# ir2104_V1_2.net
KiCad netlist of a schematic drawn in EasyEDA Pro
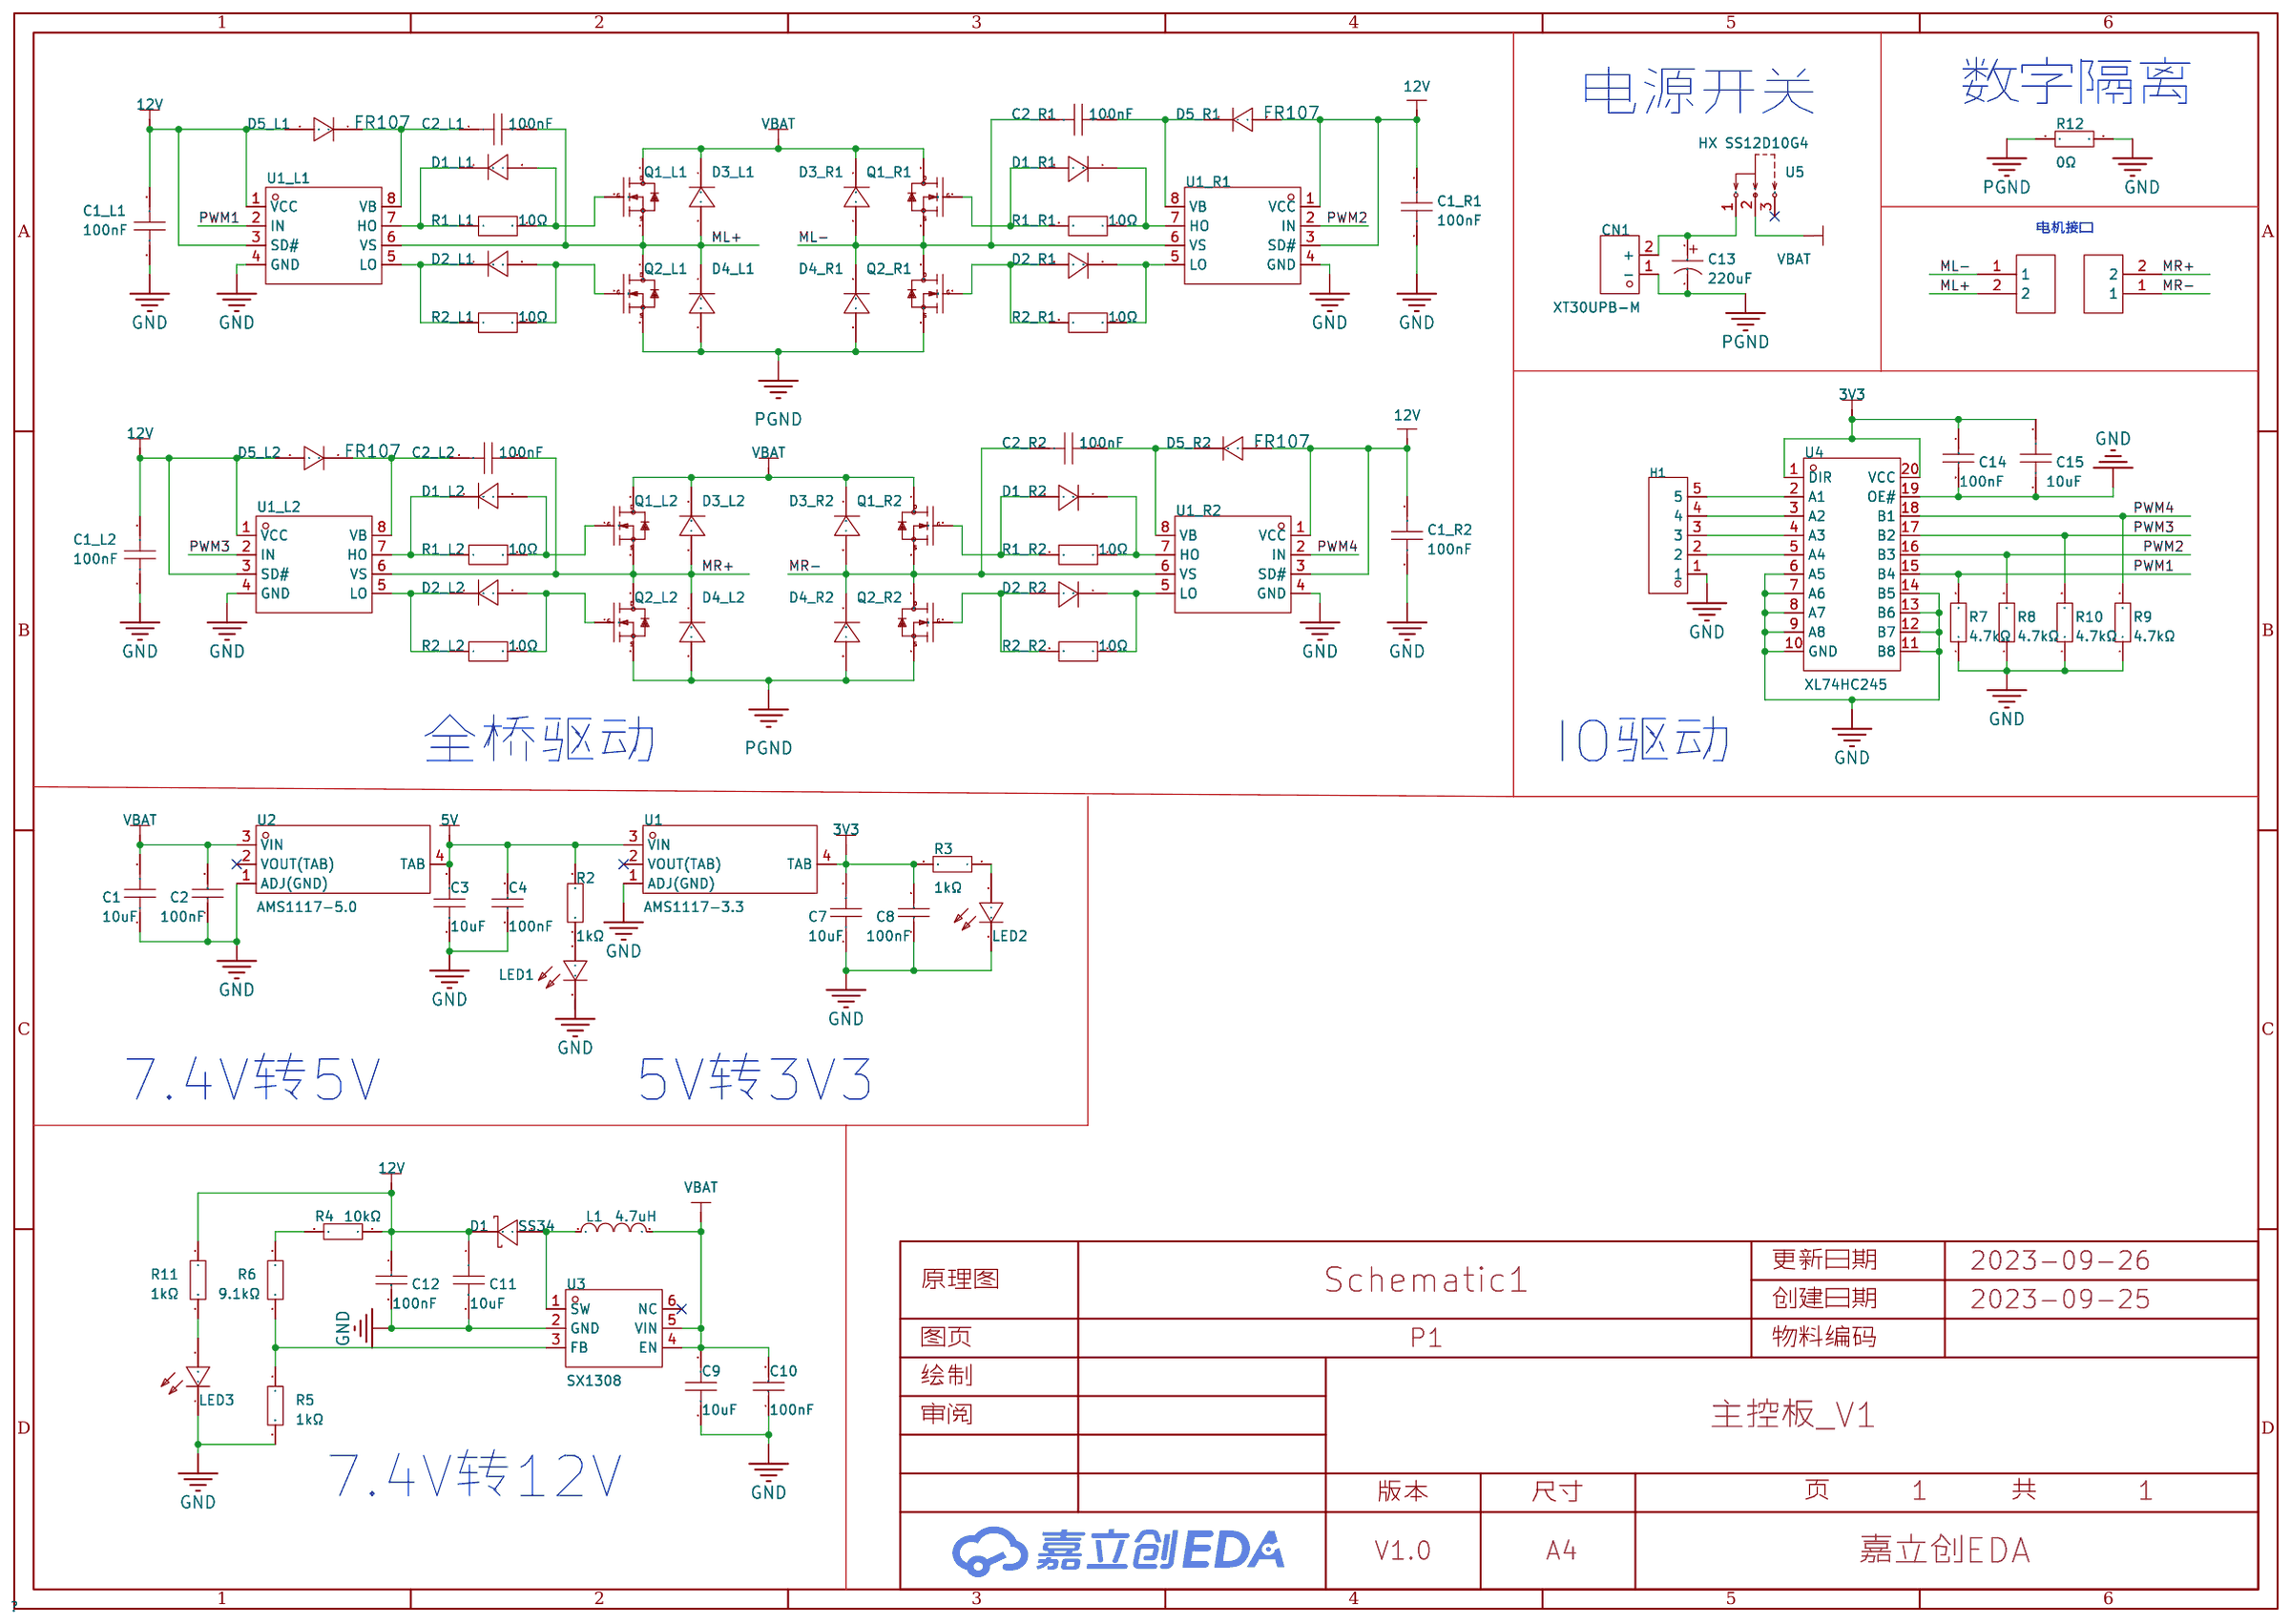
[diagram p0: schematic sheet]

(export (version "E")
  (design (tool "Eeschema 10.0.6"))
  (components
    (comp (ref "C1")
      (value "10uF")
      (footprint "easyedapro:C0603")
      (description "容值:10uF;精度:±20%;额定电压:25V;材质(温度系数):X5R;")
      (fields
        (field (name "Manufacturer Part") "CL10A106MA8NRNC")
        (field (name "Manufacturer") "SAMSUNG(三星)")
      )
      (libsource (lib "easyedapro") (part "CL10A106MA8NRNC"))
    )
    (comp (ref "C1_L1")
      (value "100nF")
      (footprint "easyedapro:C0603")
      (description "容值:100nF;精度:±10%;额定电压:50V;材质(温度系数):X7R;")
      (fields
        (field (name "Manufacturer Part") "CL10B104KB8NNNC")
        (field (name "Manufacturer") "SAMSUNG(三星)")
      )
      (libsource (lib "easyedapro") (part "CL10B104KB8NNNC"))
    )
    (comp (ref "C1_L2")
      (value "100nF")
      (footprint "easyedapro:C0603")
      (description "容值:100nF;精度:±10%;额定电压:50V;材质(温度系数):X7R;")
      (fields
        (field (name "Manufacturer Part") "CL10B104KB8NNNC")
        (field (name "Manufacturer") "SAMSUNG(三星)")
      )
      (libsource (lib "easyedapro") (part "CL10B104KB8NNNC"))
    )
    (comp (ref "C1_R1")
      (value "100nF")
      (footprint "easyedapro:C0603")
      (description "容值:100nF;精度:±10%;额定电压:50V;材质(温度系数):X7R;")
      (fields
        (field (name "Manufacturer Part") "CL10B104KB8NNNC")
        (field (name "Manufacturer") "SAMSUNG(三星)")
      )
      (libsource (lib "easyedapro") (part "CL10B104KB8NNNC"))
    )
    (comp (ref "C1_R2")
      (value "100nF")
      (footprint "easyedapro:C0603")
      (description "容值:100nF;精度:±10%;额定电压:50V;材质(温度系数):X7R;")
      (fields
        (field (name "Manufacturer Part") "CL10B104KB8NNNC")
        (field (name "Manufacturer") "SAMSUNG(三星)")
      )
      (libsource (lib "easyedapro") (part "CL10B104KB8NNNC"))
    )
    (comp (ref "C2")
      (value "100nF")
      (footprint "easyedapro:C0603")
      (description "容值:100nF;精度:±10%;额定电压:50V;材质(温度系数):X7R;")
      (fields (field (name "Manufacturer Part") "0603B104K500NT") (field (name "Manufacturer") "FH(风华)"))
      (libsource (lib "easyedapro") (part "0603B104K500NT"))
    )
    (comp (ref "C2_L1")
      (value "100nF")
      (footprint "easyedapro:C0603")
      (description "容值:100nF;精度:±10%;额定电压:50V;材质(温度系数):X7R;")
      (fields
        (field (name "Manufacturer Part") "CL10B104KB8NNNC")
        (field (name "Manufacturer") "SAMSUNG(三星)")
      )
      (libsource (lib "easyedapro") (part "CL10B104KB8NNNC"))
    )
    (comp (ref "C2_L2")
      (value "100nF")
      (footprint "easyedapro:C0603")
      (description "容值:100nF;精度:±10%;额定电压:50V;材质(温度系数):X7R;")
      (fields
        (field (name "Manufacturer Part") "CL10B104KB8NNNC")
        (field (name "Manufacturer") "SAMSUNG(三星)")
      )
      (libsource (lib "easyedapro") (part "CL10B104KB8NNNC"))
    )
    (comp (ref "C2_R1")
      (value "100nF")
      (footprint "easyedapro:C0603")
      (description "容值:100nF;精度:±10%;额定电压:50V;材质(温度系数):X7R;")
      (fields
        (field (name "Manufacturer Part") "CL10B104KB8NNNC")
        (field (name "Manufacturer") "SAMSUNG(三星)")
      )
      (libsource (lib "easyedapro") (part "CL10B104KB8NNNC"))
    )
    (comp (ref "C2_R2")
      (value "100nF")
      (footprint "easyedapro:C0603")
      (description "容值:100nF;精度:±10%;额定电压:50V;材质(温度系数):X7R;")
      (fields
        (field (name "Manufacturer Part") "CL10B104KB8NNNC")
        (field (name "Manufacturer") "SAMSUNG(三星)")
      )
      (libsource (lib "easyedapro") (part "CL10B104KB8NNNC"))
    )
    (comp (ref "C3")
      (value "10uF")
      (footprint "easyedapro:C0603")
      (description "容值:10uF;精度:±20%;额定电压:25V;材质(温度系数):X5R;")
      (fields
        (field (name "Manufacturer Part") "CL10A106MA8NRNC")
        (field (name "Manufacturer") "SAMSUNG(三星)")
      )
      (libsource (lib "easyedapro") (part "CL10A106MA8NRNC"))
    )
    (comp (ref "C4")
      (value "100nF")
      (footprint "easyedapro:C0603")
      (description "容值:100nF;精度:±10%;额定电压:50V;材质(温度系数):X7R;")
      (fields (field (name "Manufacturer Part") "0603B104K500NT") (field (name "Manufacturer") "FH(风华)"))
      (libsource (lib "easyedapro") (part "0603B104K500NT"))
    )
    (comp (ref "C7")
      (value "10uF")
      (footprint "easyedapro:C0603")
      (description "容值:10uF;精度:±20%;额定电压:25V;材质(温度系数):X5R;")
      (fields
        (field (name "Manufacturer Part") "CL10A106MA8NRNC")
        (field (name "Manufacturer") "SAMSUNG(三星)")
      )
      (libsource (lib "easyedapro") (part "CL10A106MA8NRNC"))
    )
    (comp (ref "C8")
      (value "100nF")
      (footprint "easyedapro:C0603")
      (description "容值:100nF;精度:±10%;额定电压:50V;材质(温度系数):X7R;")
      (fields (field (name "Manufacturer Part") "0603B104K500NT") (field (name "Manufacturer") "FH(风华)"))
      (libsource (lib "easyedapro") (part "0603B104K500NT"))
    )
    (comp (ref "C9")
      (value "10uF")
      (footprint "easyedapro:C0603")
      (description "容值:10uF;精度:±20%;额定电压:25V;材质(温度系数):X5R;")
      (fields
        (field (name "Manufacturer Part") "CL10A106MA8NRNC")
        (field (name "Manufacturer") "SAMSUNG(三星)")
      )
      (libsource (lib "easyedapro") (part "CL10A106MA8NRNC"))
    )
    (comp (ref "C10")
      (value "100nF")
      (footprint "easyedapro:C0603")
      (description "容值:100nF;精度:±10%;额定电压:50V;材质(温度系数):X7R;")
      (fields (field (name "Manufacturer Part") "0603B104K500NT") (field (name "Manufacturer") "FH(风华)"))
      (libsource (lib "easyedapro") (part "0603B104K500NT"))
    )
    (comp (ref "C11")
      (value "10uF")
      (footprint "easyedapro:C0603")
      (description "容值:10uF;精度:±20%;额定电压:25V;材质(温度系数):X5R;")
      (fields
        (field (name "Manufacturer Part") "CL10A106MA8NRNC")
        (field (name "Manufacturer") "SAMSUNG(三星)")
      )
      (libsource (lib "easyedapro") (part "CL10A106MA8NRNC"))
    )
    (comp (ref "C12")
      (value "100nF")
      (footprint "easyedapro:C0603")
      (description "容值:100nF;精度:±10%;额定电压:50V;材质(温度系数):X7R;")
      (fields (field (name "Manufacturer Part") "0603B104K500NT") (field (name "Manufacturer") "FH(风华)"))
      (libsource (lib "easyedapro") (part "0603B104K500NT"))
    )
    (comp (ref "C13")
      (value "220uF")
      (footprint "easyedapro:CAP-TH_BD8.0-P3.50-D0.6-FD")
      (description "容值:220uF;精度:±20%;额定电压:35V;纹波电流:-;等效串联电阻:-;")
      (fields
        (field (name "Manufacturer Part") "KM227M035F12RR0VH2FP0")
        (field (name "Manufacturer") "CX(承兴)")
      )
      (libsource (lib "easyedapro") (part "220uf/35V"))
    )
    (comp (ref "C14")
      (value "100nF")
      (footprint "easyedapro:C0603")
      (description "容值:100nF;精度:±10%;额定电压:50V;材质(温度系数):X7R;")
      (fields (field (name "Manufacturer Part") "0603B104K500NT") (field (name "Manufacturer") "FH(风华)"))
      (libsource (lib "easyedapro") (part "0603B104K500NT"))
    )
    (comp (ref "C15")
      (value "10uF")
      (footprint "easyedapro:C0603")
      (description "容值:10uF;精度:±20%;额定电压:25V;材质(温度系数):X5R;")
      (fields
        (field (name "Manufacturer Part") "CL10A106MA8NRNC")
        (field (name "Manufacturer") "SAMSUNG(三星)")
      )
      (libsource (lib "easyedapro") (part "CL10A106MA8NRNC"))
    )
    (comp (ref "CN1")
      (value "XT30UPB-M")
      (footprint "easyedapro:CONN-TH_XT30UPB-M")
      (fields (field (name "Manufacturer") "AMASS(艾迈斯)"))
      (libsource (lib "easyedapro") (part "XT30UPB-M"))
    )
    (comp (ref "D1")
      (value "SS34")
      (footprint "easyedapro:SMA_L4.3-W2.6-LS5.2-RD")
      (description "二极管配置:独立式;直流反向耐压(Vr):40V;平均整流电流(Io):3A;正向压降(Vf):550mV@3A;")
      (fields (field (name "Manufacturer") "MDD"))
      (libsource (lib "easyedapro") (part "SS34_C8678"))
    )
    (comp (ref "D1_L1")
      (value "US1M")
      (footprint "easyedapro:SMA_L4.4-W2.8-LS5.4-RD")
      (fields (field (name "Manufacturer") "MDD"))
      (libsource (lib "easyedapro") (part "US1MG_C412437"))
    )
    (comp (ref "D1_L2")
      (value "US1M")
      (footprint "easyedapro:SMA_L4.4-W2.8-LS5.4-RD")
      (fields (field (name "Manufacturer") "MDD"))
      (libsource (lib "easyedapro") (part "US1MG_C412437"))
    )
    (comp (ref "D1_R1")
      (value "US1M")
      (footprint "easyedapro:SMA_L4.4-W2.8-LS5.4-RD")
      (fields (field (name "Manufacturer") "MDD"))
      (libsource (lib "easyedapro") (part "US1MG_C412437"))
    )
    (comp (ref "D1_R2")
      (value "US1M")
      (footprint "easyedapro:SMA_L4.4-W2.8-LS5.4-RD")
      (fields (field (name "Manufacturer") "MDD"))
      (libsource (lib "easyedapro") (part "US1MG_C412437"))
    )
    (comp (ref "D2_L1")
      (value "US1M")
      (footprint "easyedapro:SMA_L4.4-W2.8-LS5.4-RD")
      (fields (field (name "Manufacturer") "MDD"))
      (libsource (lib "easyedapro") (part "US1MG_C412437"))
    )
    (comp (ref "D2_L2")
      (value "US1M")
      (footprint "easyedapro:SMA_L4.4-W2.8-LS5.4-RD")
      (fields (field (name "Manufacturer") "MDD"))
      (libsource (lib "easyedapro") (part "US1MG_C412437"))
    )
    (comp (ref "D2_R1")
      (value "US1M")
      (footprint "easyedapro:SMA_L4.4-W2.8-LS5.4-RD")
      (fields (field (name "Manufacturer") "MDD"))
      (libsource (lib "easyedapro") (part "US1MG_C412437"))
    )
    (comp (ref "D2_R2")
      (value "US1M")
      (footprint "easyedapro:SMA_L4.4-W2.8-LS5.4-RD")
      (fields (field (name "Manufacturer") "MDD"))
      (libsource (lib "easyedapro") (part "US1MG_C412437"))
    )
    (comp (ref "D3_L1")
      (value "US1M")
      (footprint "easyedapro:SMA_L4.4-W2.8-LS5.4-RD")
      (fields (field (name "Manufacturer") "MDD"))
      (libsource (lib "easyedapro") (part "US1MG_C412437"))
    )
    (comp (ref "D3_L2")
      (value "US1M")
      (footprint "easyedapro:SMA_L4.4-W2.8-LS5.4-RD")
      (fields (field (name "Manufacturer") "MDD"))
      (libsource (lib "easyedapro") (part "US1MG_C412437"))
    )
    (comp (ref "D3_R1")
      (value "US1M")
      (footprint "easyedapro:SMA_L4.4-W2.8-LS5.4-RD")
      (fields (field (name "Manufacturer") "MDD"))
      (libsource (lib "easyedapro") (part "US1MG_C412437"))
    )
    (comp (ref "D3_R2")
      (value "US1M")
      (footprint "easyedapro:SMA_L4.4-W2.8-LS5.4-RD")
      (fields (field (name "Manufacturer") "MDD"))
      (libsource (lib "easyedapro") (part "US1MG_C412437"))
    )
    (comp (ref "D4_L1")
      (value "US1M")
      (footprint "easyedapro:SMA_L4.4-W2.8-LS5.4-RD")
      (fields (field (name "Manufacturer") "MDD"))
      (libsource (lib "easyedapro") (part "US1MG_C412437"))
    )
    (comp (ref "D4_L2")
      (value "US1M")
      (footprint "easyedapro:SMA_L4.4-W2.8-LS5.4-RD")
      (fields (field (name "Manufacturer") "MDD"))
      (libsource (lib "easyedapro") (part "US1MG_C412437"))
    )
    (comp (ref "D4_R1")
      (value "US1M")
      (footprint "easyedapro:SMA_L4.4-W2.8-LS5.4-RD")
      (fields (field (name "Manufacturer") "MDD"))
      (libsource (lib "easyedapro") (part "US1MG_C412437"))
    )
    (comp (ref "D4_R2")
      (value "US1M")
      (footprint "easyedapro:SMA_L4.4-W2.8-LS5.4-RD")
      (fields (field (name "Manufacturer") "MDD"))
      (libsource (lib "easyedapro") (part "US1MG_C412437"))
    )
    (comp (ref "D5_L1")
      (value "FR107")
      (footprint "easyedapro:SOD-123_L2.8-W1.8-LS3.7-RD")
      (fields (field (name "Manufacturer") "BORN(伯恩半导体)"))
      (libsource (lib "easyedapro") (part "FR107_C511885"))
    )
    (comp (ref "D5_L2")
      (value "FR107")
      (footprint "easyedapro:SOD-123_L2.8-W1.8-LS3.7-RD")
      (fields (field (name "Manufacturer") "BORN(伯恩半导体)"))
      (libsource (lib "easyedapro") (part "FR107_C511885"))
    )
    (comp (ref "D5_R1")
      (value "FR107")
      (footprint "easyedapro:SOD-123_L2.8-W1.8-LS3.7-RD")
      (fields (field (name "Manufacturer") "BORN(伯恩半导体)"))
      (libsource (lib "easyedapro") (part "FR107_C511885"))
    )
    (comp (ref "D5_R2")
      (value "FR107")
      (footprint "easyedapro:SOD-123_L2.8-W1.8-LS3.7-RD")
      (fields (field (name "Manufacturer") "BORN(伯恩半导体)"))
      (libsource (lib "easyedapro") (part "FR107_C511885"))
    )
    (comp (ref "H1")
      (value "PZ254V-11-05P")
      (footprint "easyedapro:HDR-TH_5P-P2.54-V-M")
      (fields (field (name "Manufacturer") "XFCN(兴飞)"))
      (libsource (lib "easyedapro") (part "PZ254V-11-05P"))
    )
    (comp (ref "L1")
      (value "4.7uH")
      (footprint "easyedapro:IND-SMD_L5.4-W5.2_FXL0530")
      (description "电感值:4.7uH;精度:±20%;额定电流:4.5A;饱和电流(Isat):5A;")
      (fields (field (name "Manufacturer Part") "FXL0530-4R7-M") (field (name "Manufacturer") "cjiang(长江微电)"))
      (libsource (lib "easyedapro") (part "FXL0530-4R7-M"))
    )
    (comp (ref "LED1")
      (value "NCD0603R1")
      (footprint "easyedapro:LED0603-RD_RED")
      (description "发光颜色:红灯;")
      (fields (field (name "Manufacturer") "国星光电"))
      (libsource (lib "easyedapro") (part "FC-DA1608HRK-620D"))
    )
    (comp (ref "LED2")
      (value "NCD0603R1")
      (footprint "easyedapro:LED0603-RD_RED")
      (description "发光颜色:红灯;")
      (fields (field (name "Manufacturer") "国星光电"))
      (libsource (lib "easyedapro") (part "FC-DA1608HRK-620D"))
    )
    (comp (ref "LED3")
      (value "NCD0603R1")
      (footprint "easyedapro:LED0603-RD_RED")
      (description "发光颜色:红灯;")
      (fields (field (name "Manufacturer") "国星光电"))
      (libsource (lib "easyedapro") (part "FC-DA1608HRK-620D"))
    )
    (comp (ref "P1")
      (value "WJ500V-5.08-2P")
      (footprint "easyedapro:CONN-TH_2P-P5.00_WJ500V-5.08-2P")
      (fields (field (name "Manufacturer") "KANGNEX(康奈克斯电气)"))
      (libsource (lib "easyedapro") (part "WJ500V-5.08-2P-14-00A"))
    )
    (comp (ref "P2")
      (value "WJ500V-5.08-2P")
      (footprint "easyedapro:CONN-TH_2P-P5.00_WJ500V-5.08-2P")
      (fields (field (name "Manufacturer") "KANGNEX(康奈克斯电气)"))
      (libsource (lib "easyedapro") (part "WJ500V-5.08-2P-14-00A"))
    )
    (comp (ref "Q1_L1")
      (value "IRFR3607TRPBF")
      (footprint "easyedapro:TO-252-3_L6.5-W5.8-P4.58-BL")
      (fields (field (name "Manufacturer") "Infineon(英飞凌)"))
      (libsource (lib "easyedapro") (part "IRFR3607TRPBF"))
    )
    (comp (ref "Q1_L2")
      (value "IRFR3607TRPBF")
      (footprint "easyedapro:TO-252-3_L6.5-W5.8-P4.58-BL")
      (fields (field (name "Manufacturer") "Infineon(英飞凌)"))
      (libsource (lib "easyedapro") (part "IRFR3607TRPBF"))
    )
    (comp (ref "Q1_R1")
      (value "IRFR3607TRPBF")
      (footprint "easyedapro:TO-252-3_L6.5-W5.8-P4.58-BL")
      (fields (field (name "Manufacturer") "Infineon(英飞凌)"))
      (libsource (lib "easyedapro") (part "IRFR3607TRPBF"))
    )
    (comp (ref "Q1_R2")
      (value "IRFR3607TRPBF")
      (footprint "easyedapro:TO-252-3_L6.5-W5.8-P4.58-BL")
      (fields (field (name "Manufacturer") "Infineon(英飞凌)"))
      (libsource (lib "easyedapro") (part "IRFR3607TRPBF"))
    )
    (comp (ref "Q2_L1")
      (value "IRFR3607TRPBF")
      (footprint "easyedapro:TO-252-3_L6.5-W5.8-P4.58-BL")
      (fields (field (name "Manufacturer") "Infineon(英飞凌)"))
      (libsource (lib "easyedapro") (part "IRFR3607TRPBF"))
    )
    (comp (ref "Q2_L2")
      (value "IRFR3607TRPBF")
      (footprint "easyedapro:TO-252-3_L6.5-W5.8-P4.58-BL")
      (fields (field (name "Manufacturer") "Infineon(英飞凌)"))
      (libsource (lib "easyedapro") (part "IRFR3607TRPBF"))
    )
    (comp (ref "Q2_R1")
      (value "IRFR3607TRPBF")
      (footprint "easyedapro:TO-252-3_L6.5-W5.8-P4.58-BL")
      (fields (field (name "Manufacturer") "Infineon(英飞凌)"))
      (libsource (lib "easyedapro") (part "IRFR3607TRPBF"))
    )
    (comp (ref "Q2_R2")
      (value "IRFR3607TRPBF")
      (footprint "easyedapro:TO-252-3_L6.5-W5.8-P4.58-BL")
      (fields (field (name "Manufacturer") "Infineon(英飞凌)"))
      (libsource (lib "easyedapro") (part "IRFR3607TRPBF"))
    )
    (comp (ref "R1_L1")
      (value "10Ω")
      (footprint "easyedapro:R0603")
      (description "阻值:10Ω;精度:±0.5%;功率:250mW;")
      (fields (field (name "Manufacturer Part") "ERJUP3D10R0V") (field (name "Manufacturer") "PANASONIC(松下)"))
      (libsource (lib "easyedapro") (part "ERJUP3D10R0V"))
    )
    (comp (ref "R1_L2")
      (value "10Ω")
      (footprint "easyedapro:R0603")
      (description "阻值:10Ω;精度:±0.5%;功率:250mW;")
      (fields (field (name "Manufacturer Part") "ERJUP3D10R0V") (field (name "Manufacturer") "PANASONIC(松下)"))
      (libsource (lib "easyedapro") (part "ERJUP3D10R0V"))
    )
    (comp (ref "R1_R1")
      (value "10Ω")
      (footprint "easyedapro:R0603")
      (description "阻值:10Ω;精度:±0.5%;功率:250mW;")
      (fields (field (name "Manufacturer Part") "ERJUP3D10R0V") (field (name "Manufacturer") "PANASONIC(松下)"))
      (libsource (lib "easyedapro") (part "ERJUP3D10R0V"))
    )
    (comp (ref "R1_R2")
      (value "10Ω")
      (footprint "easyedapro:R0603")
      (description "阻值:10Ω;精度:±0.5%;功率:250mW;")
      (fields (field (name "Manufacturer Part") "ERJUP3D10R0V") (field (name "Manufacturer") "PANASONIC(松下)"))
      (libsource (lib "easyedapro") (part "ERJUP3D10R0V"))
    )
    (comp (ref "R2")
      (value "1kΩ")
      (footprint "easyedapro:R0603")
      (description "电阻类型:厚膜电阻;阻值:1kΩ;精度:±1%;功率:100mW;")
      (fields
        (field (name "Manufacturer Part") "0603WAF1001T5E")
        (field (name "Manufacturer") "UNI-ROYAL(厚声)")
      )
      (libsource (lib "easyedapro") (part "0603WAF1001T5E"))
    )
    (comp (ref "R2_L1")
      (value "10Ω")
      (footprint "easyedapro:R0603")
      (description "阻值:10Ω;精度:±0.5%;功率:250mW;")
      (fields (field (name "Manufacturer Part") "ERJUP3D10R0V") (field (name "Manufacturer") "PANASONIC(松下)"))
      (libsource (lib "easyedapro") (part "ERJUP3D10R0V"))
    )
    (comp (ref "R2_L2")
      (value "10Ω")
      (footprint "easyedapro:R0603")
      (description "阻值:10Ω;精度:±0.5%;功率:250mW;")
      (fields (field (name "Manufacturer Part") "ERJUP3D10R0V") (field (name "Manufacturer") "PANASONIC(松下)"))
      (libsource (lib "easyedapro") (part "ERJUP3D10R0V"))
    )
    (comp (ref "R2_R1")
      (value "10Ω")
      (footprint "easyedapro:R0603")
      (description "阻值:10Ω;精度:±0.5%;功率:250mW;")
      (fields (field (name "Manufacturer Part") "ERJUP3D10R0V") (field (name "Manufacturer") "PANASONIC(松下)"))
      (libsource (lib "easyedapro") (part "ERJUP3D10R0V"))
    )
    (comp (ref "R2_R2")
      (value "10Ω")
      (footprint "easyedapro:R0603")
      (description "阻值:10Ω;精度:±0.5%;功率:250mW;")
      (fields (field (name "Manufacturer Part") "ERJUP3D10R0V") (field (name "Manufacturer") "PANASONIC(松下)"))
      (libsource (lib "easyedapro") (part "ERJUP3D10R0V"))
    )
    (comp (ref "R3")
      (value "1kΩ")
      (footprint "easyedapro:R0603")
      (description "电阻类型:厚膜电阻;阻值:1kΩ;精度:±1%;功率:100mW;")
      (fields
        (field (name "Manufacturer Part") "0603WAF1001T5E")
        (field (name "Manufacturer") "UNI-ROYAL(厚声)")
      )
      (libsource (lib "easyedapro") (part "0603WAF1001T5E"))
    )
    (comp (ref "R4")
      (value "10kΩ")
      (footprint "easyedapro:R0603")
      (description "电阻类型:薄膜电阻;阻值:10kΩ;精度:±0.1%;功率:100mW;")
      (fields (field (name "Manufacturer Part") "RT0603BRD0710KL") (field (name "Manufacturer") "YAGEO(国巨)"))
      (libsource (lib "easyedapro") (part "RT0603BRD0710KL"))
    )
    (comp (ref "R5")
      (value "1kΩ")
      (footprint "easyedapro:R0603")
      (description "电阻类型:薄膜电阻;阻值:1kΩ;精度:±0.1%;功率:100mW;")
      (fields (field (name "Manufacturer Part") "RT0603BRD071KL") (field (name "Manufacturer") "YAGEO(国巨)"))
      (libsource (lib "easyedapro") (part "RT0603BRD071KL"))
    )
    (comp (ref "R6")
      (value "9.1kΩ")
      (footprint "easyedapro:R0603")
      (description "电阻类型:薄膜电阻;阻值:9.1kΩ;精度:±0.1%;功率:100mW;")
      (fields (field (name "Manufacturer Part") "PTFR0603B9K10P9") (field (name "Manufacturer") "RESI(开步睿思）"))
      (libsource (lib "easyedapro") (part "PTFR0603B9K10P9"))
    )
    (comp (ref "R7")
      (value "4.7kΩ")
      (footprint "easyedapro:R0603")
      (description "电阻类型:厚膜电阻;阻值:4.7kΩ;精度:±1%;功率:100mW;")
      (fields
        (field (name "Manufacturer Part") "0603WAF4701T5E")
        (field (name "Manufacturer") "UNI-ROYAL(厚声)")
      )
      (libsource (lib "easyedapro") (part "0603WAF4701T5E"))
    )
    (comp (ref "R8")
      (value "4.7kΩ")
      (footprint "easyedapro:R0603")
      (description "电阻类型:厚膜电阻;阻值:4.7kΩ;精度:±1%;功率:100mW;")
      (fields
        (field (name "Manufacturer Part") "0603WAF4701T5E")
        (field (name "Manufacturer") "UNI-ROYAL(厚声)")
      )
      (libsource (lib "easyedapro") (part "0603WAF4701T5E"))
    )
    (comp (ref "R9")
      (value "4.7kΩ")
      (footprint "easyedapro:R0603")
      (description "电阻类型:厚膜电阻;阻值:4.7kΩ;精度:±1%;功率:100mW;")
      (fields
        (field (name "Manufacturer Part") "0603WAF4701T5E")
        (field (name "Manufacturer") "UNI-ROYAL(厚声)")
      )
      (libsource (lib "easyedapro") (part "0603WAF4701T5E"))
    )
    (comp (ref "R10")
      (value "4.7kΩ")
      (footprint "easyedapro:R0603")
      (description "电阻类型:厚膜电阻;阻值:4.7kΩ;精度:±1%;功率:100mW;")
      (fields
        (field (name "Manufacturer Part") "0603WAF4701T5E")
        (field (name "Manufacturer") "UNI-ROYAL(厚声)")
      )
      (libsource (lib "easyedapro") (part "0603WAF4701T5E"))
    )
    (comp (ref "R11")
      (value "1kΩ")
      (footprint "easyedapro:R0603")
      (description "电阻类型:厚膜电阻;阻值:1kΩ;精度:±1%;功率:100mW;")
      (fields
        (field (name "Manufacturer Part") "0603WAF1001T5E")
        (field (name "Manufacturer") "UNI-ROYAL(厚声)")
      )
      (libsource (lib "easyedapro") (part "0603WAF1001T5E"))
    )
    (comp (ref "R12")
      (value "0Ω")
      (footprint "easyedapro:R0805")
      (description "电阻类型:厚膜电阻;阻值:0Ω;精度:±1%;功率:125mW;")
      (fields
        (field (name "Manufacturer Part") "0805W8F0000T5E")
        (field (name "Manufacturer") "UNI-ROYAL(厚声)")
      )
      (libsource (lib "easyedapro") (part "0805W8F0000T5E"))
    )
    (comp (ref "U1")
      (value "AMS1117-3.3")
      (footprint "easyedapro:SOT-223-4_L6.5-W3.5-P2.30-LS7.0-BR")
      (description "输出类型:固定;输出极性:正;最大输入电压:18V;输出电压:3.3V;输出电流:1A;电源纹波抑制比(PSRR):60dB@(120Hz);")
      (fields (field (name "Manufacturer") "UMW(广东友台半导体)"))
      (libsource (lib "easyedapro") (part "AMS1117-3.3_C347222"))
    )
    (comp (ref "U1_L1")
      (value "EG2104")
      (footprint "easyedapro:SOP-8_L5.0-W4.0-P1.27-LS6.2-BL")
      (description "高性价比, 600V，半桥式Nmos预驱动器")
      (fields (field (name "Manufacturer") "EG(屹晶微)"))
      (libsource (lib "easyedapro") (part "EG2104"))
    )
    (comp (ref "U1_L2")
      (value "EG2104")
      (footprint "easyedapro:SOP-8_L5.0-W4.0-P1.27-LS6.2-BL")
      (description "高性价比, 600V，半桥式Nmos预驱动器")
      (fields (field (name "Manufacturer") "EG(屹晶微)"))
      (libsource (lib "easyedapro") (part "EG2104"))
    )
    (comp (ref "U1_R1")
      (value "EG2104")
      (footprint "easyedapro:SOP-8_L5.0-W4.0-P1.27-LS6.2-BL")
      (description "高性价比, 600V，半桥式Nmos预驱动器")
      (fields (field (name "Manufacturer") "EG(屹晶微)"))
      (libsource (lib "easyedapro") (part "EG2104"))
    )
    (comp (ref "U1_R2")
      (value "EG2104")
      (footprint "easyedapro:SOP-8_L5.0-W4.0-P1.27-LS6.2-BL")
      (description "高性价比, 600V，半桥式Nmos预驱动器")
      (fields (field (name "Manufacturer") "EG(屹晶微)"))
      (libsource (lib "easyedapro") (part "EG2104"))
    )
    (comp (ref "U2")
      (value "AMS1117-5.0")
      (footprint "easyedapro:SOT-223_L6.7-W3.5-P2.30-BR")
      (description "输出类型:固定;输出极性:正;最大输入电压:18V;输出电压:5V;输出电流:1A;电源纹波抑制比(PSRR):60dB@(120Hz);")
      (fields (field (name "Manufacturer") "UMW(广东友台半导体)"))
      (libsource (lib "easyedapro") (part "AMS1117-5.0_C347223"))
    )
    (comp (ref "U3")
      (value "SX1308")
      (footprint "easyedapro:SOT-23-6_L2.9-W1.6-P0.95-LS2.8-BL")
      (description "功能类型:升压型;同步整流:否;输出通道数:1;拓扑结构:升压式;输入电压:2V~24V;输出电压:28V;输出电流(最大值):-;开关频率:1.2MHz;")
      (fields (field (name "Manufacturer") "SX(硕芯科技)"))
      (libsource (lib "easyedapro") (part "SX1308"))
    )
    (comp (ref "U4")
      (value "XL74HC245")
      (footprint "easyedapro:SOP-20_L12.8-W7.5-P1.27-LS10.4-BL")
      (description "八路总线收发器")
      (fields (field (name "Manufacturer") "XINLUDA(信路达)"))
      (libsource (lib "easyedapro") (part "XL74HC245"))
    )
    (comp (ref "U5")
      (value "HX SS12D10G4")
      (footprint "easyedapro:SW-TH_SHOU-HAN_SS12D10G4")
      (fields (field (name "Manufacturer") "hanxia(韩下)"))
      (libsource (lib "easyedapro") (part "HX SS12D10G4"))
    )
  )
  (nets
    (net (code "1") (name "/ML+") (class "Default")
      (node (ref "C2_L1") (pin "2") (pinfunction "2_2") (pintype "input"))
      (node (ref "D3_L1") (pin "2") (pinfunction "A_2") (pintype "input"))
      (node (ref "D4_L1") (pin "1") (pinfunction "C_1") (pintype "input"))
      (node (ref "P1") (pin "2") (pinfunction "2_2") (pintype "input"))
      (node (ref "Q1_L1") (pin "3") (pinfunction "S_3") (pintype "input"))
      (node (ref "Q2_L1") (pin "2") (pinfunction "D_2") (pintype "input"))
      (node (ref "U1_L1") (pin "6") (pinfunction "VS_6") (pintype "input"))
    )
    (net (code "2") (name "/ML-") (class "Default")
      (node (ref "C2_R1") (pin "2") (pinfunction "2_2") (pintype "input"))
      (node (ref "D3_R1") (pin "2") (pinfunction "A_2") (pintype "input"))
      (node (ref "D4_R1") (pin "1") (pinfunction "C_1") (pintype "input"))
      (node (ref "P1") (pin "1") (pinfunction "1_1") (pintype "input"))
      (node (ref "Q1_R1") (pin "3") (pinfunction "S_3") (pintype "input"))
      (node (ref "Q2_R1") (pin "2") (pinfunction "D_2") (pintype "input"))
      (node (ref "U1_R1") (pin "6") (pinfunction "VS_6") (pintype "input"))
    )
    (net (code "3") (name "/MR+") (class "Default")
      (node (ref "C2_L2") (pin "2") (pinfunction "2_2") (pintype "input"))
      (node (ref "D3_L2") (pin "2") (pinfunction "A_2") (pintype "input"))
      (node (ref "D4_L2") (pin "1") (pinfunction "C_1") (pintype "input"))
      (node (ref "P2") (pin "2") (pinfunction "2_2") (pintype "input"))
      (node (ref "Q1_L2") (pin "3") (pinfunction "S_3") (pintype "input"))
      (node (ref "Q2_L2") (pin "2") (pinfunction "D_2") (pintype "input"))
      (node (ref "U1_L2") (pin "6") (pinfunction "VS_6") (pintype "input"))
    )
    (net (code "4") (name "/MR-") (class "Default")
      (node (ref "C2_R2") (pin "2") (pinfunction "2_2") (pintype "input"))
      (node (ref "D3_R2") (pin "2") (pinfunction "A_2") (pintype "input"))
      (node (ref "D4_R2") (pin "1") (pinfunction "C_1") (pintype "input"))
      (node (ref "P2") (pin "1") (pinfunction "1_1") (pintype "input"))
      (node (ref "Q1_R2") (pin "3") (pinfunction "S_3") (pintype "input"))
      (node (ref "Q2_R2") (pin "2") (pinfunction "D_2") (pintype "input"))
      (node (ref "U1_R2") (pin "6") (pinfunction "VS_6") (pintype "input"))
    )
    (net (code "5") (name "/PWM1") (class "Default")
      (node (ref "R7") (pin "2") (pinfunction "2_2") (pintype "input"))
      (node (ref "U1_L1") (pin "2") (pinfunction "IN_2") (pintype "input"))
      (node (ref "U4") (pin "15") (pinfunction "B4_15") (pintype "input"))
    )
    (net (code "6") (name "/PWM2") (class "Default")
      (node (ref "R8") (pin "2") (pinfunction "2_2") (pintype "input"))
      (node (ref "U1_R1") (pin "2") (pinfunction "IN_2") (pintype "input"))
      (node (ref "U4") (pin "16") (pinfunction "B3_16") (pintype "input"))
    )
    (net (code "7") (name "/PWM3") (class "Default")
      (node (ref "R10") (pin "2") (pinfunction "2_2") (pintype "input"))
      (node (ref "U1_L2") (pin "2") (pinfunction "IN_2") (pintype "input"))
      (node (ref "U4") (pin "17") (pinfunction "B2_17") (pintype "input"))
    )
    (net (code "8") (name "/PWM4") (class "Default")
      (node (ref "R9") (pin "2") (pinfunction "2_2") (pintype "input"))
      (node (ref "U1_R2") (pin "2") (pinfunction "IN_2") (pintype "input"))
      (node (ref "U4") (pin "18") (pinfunction "B1_18") (pintype "input"))
    )
    (net (code "9") (name "3V3") (class "Default")
      (node (ref "C14") (pin "1") (pinfunction "1_1") (pintype "input"))
      (node (ref "C15") (pin "1") (pinfunction "1_1") (pintype "input"))
      (node (ref "C7") (pin "2") (pinfunction "2_2") (pintype "input"))
      (node (ref "C8") (pin "2") (pinfunction "2_2") (pintype "input"))
      (node (ref "R3") (pin "2") (pinfunction "2_2") (pintype "input"))
      (node (ref "U1") (pin "4") (pinfunction "TAB_4") (pintype "input"))
      (node (ref "U4") (pin "1") (pinfunction "DIR_1") (pintype "input"))
      (node (ref "U4") (pin "20") (pinfunction "VCC_20") (pintype "input"))
    )
    (net (code "10") (name "5V") (class "Default")
      (node (ref "C3") (pin "2") (pinfunction "2_2") (pintype "input"))
      (node (ref "C4") (pin "2") (pinfunction "2_2") (pintype "input"))
      (node (ref "R2") (pin "1") (pinfunction "1_1") (pintype "input"))
      (node (ref "U1") (pin "3") (pinfunction "VIN_3") (pintype "input"))
      (node (ref "U2") (pin "4") (pinfunction "TAB_4") (pintype "input"))
    )
    (net (code "11") (name "12V") (class "Default")
      (node (ref "C11") (pin "1") (pinfunction "1_1") (pintype "input"))
      (node (ref "C12") (pin "1") (pinfunction "1_1") (pintype "input"))
      (node (ref "C1_L1") (pin "2") (pinfunction "2_2") (pintype "input"))
      (node (ref "C1_L2") (pin "2") (pinfunction "2_2") (pintype "input"))
      (node (ref "C1_R1") (pin "2") (pinfunction "2_2") (pintype "input"))
      (node (ref "C1_R2") (pin "2") (pinfunction "2_2") (pintype "input"))
      (node (ref "D1") (pin "1") (pinfunction "K_1") (pintype "input"))
      (node (ref "D5_L1") (pin "2") (pinfunction "A_2") (pintype "input"))
      (node (ref "D5_L2") (pin "2") (pinfunction "A_2") (pintype "input"))
      (node (ref "D5_R1") (pin "2") (pinfunction "A_2") (pintype "input"))
      (node (ref "D5_R2") (pin "2") (pinfunction "A_2") (pintype "input"))
      (node (ref "R11") (pin "1") (pinfunction "1_1") (pintype "input"))
      (node (ref "R4") (pin "1") (pinfunction "1_1") (pintype "input"))
      (node (ref "U1_L1") (pin "1") (pinfunction "VCC_1") (pintype "input"))
      (node (ref "U1_L1") (pin "3") (pinfunction "SD#_3") (pintype "input"))
      (node (ref "U1_L2") (pin "1") (pinfunction "VCC_1") (pintype "input"))
      (node (ref "U1_L2") (pin "3") (pinfunction "SD#_3") (pintype "input"))
      (node (ref "U1_R1") (pin "1") (pinfunction "VCC_1") (pintype "input"))
      (node (ref "U1_R1") (pin "3") (pinfunction "SD#_3") (pintype "input"))
      (node (ref "U1_R2") (pin "1") (pinfunction "VCC_1") (pintype "input"))
      (node (ref "U1_R2") (pin "3") (pinfunction "SD#_3") (pintype "input"))
    )
    (net (code "12") (name "GND") (class "Default")
      (node (ref "C1") (pin "1") (pinfunction "1_1") (pintype "input"))
      (node (ref "C10") (pin "1") (pinfunction "1_1") (pintype "input"))
      (node (ref "C11") (pin "2") (pinfunction "2_2") (pintype "input"))
      (node (ref "C12") (pin "2") (pinfunction "2_2") (pintype "input"))
      (node (ref "C14") (pin "2") (pinfunction "2_2") (pintype "input"))
      (node (ref "C15") (pin "2") (pinfunction "2_2") (pintype "input"))
      (node (ref "C1_L1") (pin "1") (pinfunction "1_1") (pintype "input"))
      (node (ref "C1_L2") (pin "1") (pinfunction "1_1") (pintype "input"))
      (node (ref "C1_R1") (pin "1") (pinfunction "1_1") (pintype "input"))
      (node (ref "C1_R2") (pin "1") (pinfunction "1_1") (pintype "input"))
      (node (ref "C2") (pin "1") (pinfunction "1_1") (pintype "input"))
      (node (ref "C3") (pin "1") (pinfunction "1_1") (pintype "input"))
      (node (ref "C4") (pin "1") (pinfunction "1_1") (pintype "input"))
      (node (ref "C7") (pin "1") (pinfunction "1_1") (pintype "input"))
      (node (ref "C8") (pin "1") (pinfunction "1_1") (pintype "input"))
      (node (ref "C9") (pin "1") (pinfunction "1_1") (pintype "input"))
      (node (ref "H1") (pin "1") (pinfunction "1_1") (pintype "input"))
      (node (ref "LED1") (pin "1") (pinfunction "K_1") (pintype "input"))
      (node (ref "LED2") (pin "1") (pinfunction "K_1") (pintype "input"))
      (node (ref "LED3") (pin "1") (pinfunction "K_1") (pintype "input"))
      (node (ref "R10") (pin "1") (pinfunction "1_1") (pintype "input"))
      (node (ref "R12") (pin "2") (pinfunction "2_2") (pintype "input"))
      (node (ref "R5") (pin "2") (pinfunction "2_2") (pintype "input"))
      (node (ref "R7") (pin "1") (pinfunction "1_1") (pintype "input"))
      (node (ref "R8") (pin "1") (pinfunction "1_1") (pintype "input"))
      (node (ref "R9") (pin "1") (pinfunction "1_1") (pintype "input"))
      (node (ref "U1") (pin "1") (pinfunction "ADJ(GND)_1") (pintype "input"))
      (node (ref "U1_L1") (pin "4") (pinfunction "GND_4") (pintype "input"))
      (node (ref "U1_L2") (pin "4") (pinfunction "GND_4") (pintype "input"))
      (node (ref "U1_R1") (pin "4") (pinfunction "GND_4") (pintype "input"))
      (node (ref "U1_R2") (pin "4") (pinfunction "GND_4") (pintype "input"))
      (node (ref "U2") (pin "1") (pinfunction "ADJ(GND)_1") (pintype "input"))
      (node (ref "U3") (pin "2") (pinfunction "GND_2") (pintype "input"))
      (node (ref "U4") (pin "10") (pinfunction "GND_10") (pintype "input"))
      (node (ref "U4") (pin "11") (pinfunction "B8_11") (pintype "input"))
      (node (ref "U4") (pin "12") (pinfunction "B7_12") (pintype "input"))
      (node (ref "U4") (pin "13") (pinfunction "B6_13") (pintype "input"))
      (node (ref "U4") (pin "14") (pinfunction "B5_14") (pintype "input"))
      (node (ref "U4") (pin "19") (pinfunction "OE#_19") (pintype "input"))
      (node (ref "U4") (pin "6") (pinfunction "A5_6") (pintype "input"))
      (node (ref "U4") (pin "7") (pinfunction "A6_7") (pintype "input"))
      (node (ref "U4") (pin "8") (pinfunction "A7_8") (pintype "input"))
      (node (ref "U4") (pin "9") (pinfunction "A8_9") (pintype "input"))
    )
    (net (code "13") (name "Net-(CN1-+)") (class "Default")
      (node (ref "C13") (pin "1") (pinfunction "1_1") (pintype "input"))
      (node (ref "CN1") (pin "2") (pinfunction "+_2") (pintype "input"))
      (node (ref "U5") (pin "1") (pinfunction "1_1") (pintype "input"))
    )
    (net (code "14") (name "Net-(D1-A)") (class "Default")
      (node (ref "D1") (pin "2") (pinfunction "A_2") (pintype "input"))
      (node (ref "L1") (pin "1") (pinfunction "1_1") (pintype "input"))
      (node (ref "U3") (pin "1") (pinfunction "SW_1") (pintype "input"))
    )
    (net (code "15") (name "Net-(D1_L1-A)") (class "Default")
      (node (ref "D1_L1") (pin "2") (pinfunction "A_2") (pintype "input"))
      (node (ref "Q1_L1") (pin "1") (pinfunction "G_1") (pintype "input"))
      (node (ref "R1_L1") (pin "2") (pinfunction "2_2") (pintype "input"))
    )
    (net (code "16") (name "Net-(D1_L1-C)") (class "Default")
      (node (ref "D1_L1") (pin "1") (pinfunction "C_1") (pintype "input"))
      (node (ref "R1_L1") (pin "1") (pinfunction "1_1") (pintype "input"))
      (node (ref "U1_L1") (pin "7") (pinfunction "HO_7") (pintype "input"))
    )
    (net (code "17") (name "Net-(D1_L2-A)") (class "Default")
      (node (ref "D1_L2") (pin "2") (pinfunction "A_2") (pintype "input"))
      (node (ref "Q1_L2") (pin "1") (pinfunction "G_1") (pintype "input"))
      (node (ref "R1_L2") (pin "2") (pinfunction "2_2") (pintype "input"))
    )
    (net (code "18") (name "Net-(D1_L2-C)") (class "Default")
      (node (ref "D1_L2") (pin "1") (pinfunction "C_1") (pintype "input"))
      (node (ref "R1_L2") (pin "1") (pinfunction "1_1") (pintype "input"))
      (node (ref "U1_L2") (pin "7") (pinfunction "HO_7") (pintype "input"))
    )
    (net (code "19") (name "Net-(D1_R1-A)") (class "Default")
      (node (ref "D1_R1") (pin "2") (pinfunction "A_2") (pintype "input"))
      (node (ref "Q1_R1") (pin "1") (pinfunction "G_1") (pintype "input"))
      (node (ref "R1_R1") (pin "2") (pinfunction "2_2") (pintype "input"))
    )
    (net (code "20") (name "Net-(D1_R1-C)") (class "Default")
      (node (ref "D1_R1") (pin "1") (pinfunction "C_1") (pintype "input"))
      (node (ref "R1_R1") (pin "1") (pinfunction "1_1") (pintype "input"))
      (node (ref "U1_R1") (pin "7") (pinfunction "HO_7") (pintype "input"))
    )
    (net (code "21") (name "Net-(D1_R2-A)") (class "Default")
      (node (ref "D1_R2") (pin "2") (pinfunction "A_2") (pintype "input"))
      (node (ref "Q1_R2") (pin "1") (pinfunction "G_1") (pintype "input"))
      (node (ref "R1_R2") (pin "2") (pinfunction "2_2") (pintype "input"))
    )
    (net (code "22") (name "Net-(D1_R2-C)") (class "Default")
      (node (ref "D1_R2") (pin "1") (pinfunction "C_1") (pintype "input"))
      (node (ref "R1_R2") (pin "1") (pinfunction "1_1") (pintype "input"))
      (node (ref "U1_R2") (pin "7") (pinfunction "HO_7") (pintype "input"))
    )
    (net (code "23") (name "Net-(D2_L1-A)") (class "Default")
      (node (ref "D2_L1") (pin "2") (pinfunction "A_2") (pintype "input"))
      (node (ref "Q2_L1") (pin "1") (pinfunction "G_1") (pintype "input"))
      (node (ref "R2_L1") (pin "2") (pinfunction "2_2") (pintype "input"))
    )
    (net (code "24") (name "Net-(D2_L1-C)") (class "Default")
      (node (ref "D2_L1") (pin "1") (pinfunction "C_1") (pintype "input"))
      (node (ref "R2_L1") (pin "1") (pinfunction "1_1") (pintype "input"))
      (node (ref "U1_L1") (pin "5") (pinfunction "LO_5") (pintype "input"))
    )
    (net (code "25") (name "Net-(D2_L2-A)") (class "Default")
      (node (ref "D2_L2") (pin "2") (pinfunction "A_2") (pintype "input"))
      (node (ref "Q2_L2") (pin "1") (pinfunction "G_1") (pintype "input"))
      (node (ref "R2_L2") (pin "2") (pinfunction "2_2") (pintype "input"))
    )
    (net (code "26") (name "Net-(D2_L2-C)") (class "Default")
      (node (ref "D2_L2") (pin "1") (pinfunction "C_1") (pintype "input"))
      (node (ref "R2_L2") (pin "1") (pinfunction "1_1") (pintype "input"))
      (node (ref "U1_L2") (pin "5") (pinfunction "LO_5") (pintype "input"))
    )
    (net (code "27") (name "Net-(D2_R1-A)") (class "Default")
      (node (ref "D2_R1") (pin "2") (pinfunction "A_2") (pintype "input"))
      (node (ref "Q2_R1") (pin "1") (pinfunction "G_1") (pintype "input"))
      (node (ref "R2_R1") (pin "2") (pinfunction "2_2") (pintype "input"))
    )
    (net (code "28") (name "Net-(D2_R1-C)") (class "Default")
      (node (ref "D2_R1") (pin "1") (pinfunction "C_1") (pintype "input"))
      (node (ref "R2_R1") (pin "1") (pinfunction "1_1") (pintype "input"))
      (node (ref "U1_R1") (pin "5") (pinfunction "LO_5") (pintype "input"))
    )
    (net (code "29") (name "Net-(D2_R2-A)") (class "Default")
      (node (ref "D2_R2") (pin "2") (pinfunction "A_2") (pintype "input"))
      (node (ref "Q2_R2") (pin "1") (pinfunction "G_1") (pintype "input"))
      (node (ref "R2_R2") (pin "2") (pinfunction "2_2") (pintype "input"))
    )
    (net (code "30") (name "Net-(D2_R2-C)") (class "Default")
      (node (ref "D2_R2") (pin "1") (pinfunction "C_1") (pintype "input"))
      (node (ref "R2_R2") (pin "1") (pinfunction "1_1") (pintype "input"))
      (node (ref "U1_R2") (pin "5") (pinfunction "LO_5") (pintype "input"))
    )
    (net (code "31") (name "Net-(D5_L1-K)") (class "Default")
      (node (ref "C2_L1") (pin "1") (pinfunction "1_1") (pintype "input"))
      (node (ref "D5_L1") (pin "1") (pinfunction "K_1") (pintype "input"))
      (node (ref "U1_L1") (pin "8") (pinfunction "VB_8") (pintype "input"))
    )
    (net (code "32") (name "Net-(D5_L2-K)") (class "Default")
      (node (ref "C2_L2") (pin "1") (pinfunction "1_1") (pintype "input"))
      (node (ref "D5_L2") (pin "1") (pinfunction "K_1") (pintype "input"))
      (node (ref "U1_L2") (pin "8") (pinfunction "VB_8") (pintype "input"))
    )
    (net (code "33") (name "Net-(D5_R1-K)") (class "Default")
      (node (ref "C2_R1") (pin "1") (pinfunction "1_1") (pintype "input"))
      (node (ref "D5_R1") (pin "1") (pinfunction "K_1") (pintype "input"))
      (node (ref "U1_R1") (pin "8") (pinfunction "VB_8") (pintype "input"))
    )
    (net (code "34") (name "Net-(D5_R2-K)") (class "Default")
      (node (ref "C2_R2") (pin "1") (pinfunction "1_1") (pintype "input"))
      (node (ref "D5_R2") (pin "1") (pinfunction "K_1") (pintype "input"))
      (node (ref "U1_R2") (pin "8") (pinfunction "VB_8") (pintype "input"))
    )
    (net (code "35") (name "Net-(LED1-A)") (class "Default")
      (node (ref "LED1") (pin "2") (pinfunction "A_2") (pintype "input"))
      (node (ref "R2") (pin "2") (pinfunction "2_2") (pintype "input"))
    )
    (net (code "36") (name "Net-(LED2-A)") (class "Default")
      (node (ref "LED2") (pin "2") (pinfunction "A_2") (pintype "input"))
      (node (ref "R3") (pin "1") (pinfunction "1_1") (pintype "input"))
    )
    (net (code "37") (name "Net-(LED3-A)") (class "Default")
      (node (ref "LED3") (pin "2") (pinfunction "A_2") (pintype "input"))
      (node (ref "R11") (pin "2") (pinfunction "2_2") (pintype "input"))
    )
    (net (code "38") (name "Net-(R4-Pad2)") (class "Default")
      (node (ref "R4") (pin "2") (pinfunction "2_2") (pintype "input"))
      (node (ref "R6") (pin "2") (pinfunction "2_2") (pintype "input"))
    )
    (net (code "39") (name "Net-(U3-FB)") (class "Default")
      (node (ref "R5") (pin "1") (pinfunction "1_1") (pintype "input"))
      (node (ref "R6") (pin "1") (pinfunction "1_1") (pintype "input"))
      (node (ref "U3") (pin "3") (pinfunction "FB_3") (pintype "input"))
    )
    (net (code "40") (name "Net-(U4-A1)") (class "Default")
      (node (ref "H1") (pin "5") (pinfunction "5_5") (pintype "input"))
      (node (ref "U4") (pin "2") (pinfunction "A1_2") (pintype "input"))
    )
    (net (code "41") (name "Net-(U4-A2)") (class "Default")
      (node (ref "H1") (pin "4") (pinfunction "4_4") (pintype "input"))
      (node (ref "U4") (pin "3") (pinfunction "A2_3") (pintype "input"))
    )
    (net (code "42") (name "Net-(U4-A3)") (class "Default")
      (node (ref "H1") (pin "3") (pinfunction "3_3") (pintype "input"))
      (node (ref "U4") (pin "4") (pinfunction "A3_4") (pintype "input"))
    )
    (net (code "43") (name "Net-(U4-A4)") (class "Default")
      (node (ref "H1") (pin "2") (pinfunction "2_2") (pintype "input"))
      (node (ref "U4") (pin "5") (pinfunction "A4_5") (pintype "input"))
    )
    (net (code "44") (name "PGND") (class "Default")
      (node (ref "C13") (pin "2") (pinfunction "2_2") (pintype "input"))
      (node (ref "CN1") (pin "1") (pinfunction "-_1") (pintype "input"))
      (node (ref "D4_L1") (pin "2") (pinfunction "A_2") (pintype "input"))
      (node (ref "D4_L2") (pin "2") (pinfunction "A_2") (pintype "input"))
      (node (ref "D4_R1") (pin "2") (pinfunction "A_2") (pintype "input"))
      (node (ref "D4_R2") (pin "2") (pinfunction "A_2") (pintype "input"))
      (node (ref "Q2_L1") (pin "3") (pinfunction "S_3") (pintype "input"))
      (node (ref "Q2_L2") (pin "3") (pinfunction "S_3") (pintype "input"))
      (node (ref "Q2_R1") (pin "3") (pinfunction "S_3") (pintype "input"))
      (node (ref "Q2_R2") (pin "3") (pinfunction "S_3") (pintype "input"))
      (node (ref "R12") (pin "1") (pinfunction "1_1") (pintype "input"))
    )
    (net (code "45") (name "VBAT") (class "Default")
      (node (ref "C1") (pin "2") (pinfunction "2_2") (pintype "input"))
      (node (ref "C10") (pin "2") (pinfunction "2_2") (pintype "input"))
      (node (ref "C2") (pin "2") (pinfunction "2_2") (pintype "input"))
      (node (ref "C9") (pin "2") (pinfunction "2_2") (pintype "input"))
      (node (ref "D3_L1") (pin "1") (pinfunction "C_1") (pintype "input"))
      (node (ref "D3_L2") (pin "1") (pinfunction "C_1") (pintype "input"))
      (node (ref "D3_R1") (pin "1") (pinfunction "C_1") (pintype "input"))
      (node (ref "D3_R2") (pin "1") (pinfunction "C_1") (pintype "input"))
      (node (ref "L1") (pin "2") (pinfunction "2_2") (pintype "input"))
      (node (ref "Q1_L1") (pin "2") (pinfunction "D_2") (pintype "input"))
      (node (ref "Q1_L2") (pin "2") (pinfunction "D_2") (pintype "input"))
      (node (ref "Q1_R1") (pin "2") (pinfunction "D_2") (pintype "input"))
      (node (ref "Q1_R2") (pin "2") (pinfunction "D_2") (pintype "input"))
      (node (ref "U2") (pin "3") (pinfunction "VIN_3") (pintype "input"))
      (node (ref "U3") (pin "4") (pinfunction "EN_4") (pintype "input"))
      (node (ref "U3") (pin "5") (pinfunction "VIN_5") (pintype "input"))
      (node (ref "U5") (pin "2") (pinfunction "2_2") (pintype "input"))
    )
    (net (code "46") (name "unconnected-(U1-VOUT(TAB)-Pad2)") (class "Default")
      (node (ref "U1") (pin "2") (pinfunction "VOUT(TAB)_2") (pintype "input+no_connect"))
    )
    (net (code "47") (name "unconnected-(U2-VOUT(TAB)-Pad2)") (class "Default")
      (node (ref "U2") (pin "2") (pinfunction "VOUT(TAB)_2") (pintype "input+no_connect"))
    )
    (net (code "48") (name "unconnected-(U3-NC-Pad6)") (class "Default")
      (node (ref "U3") (pin "6") (pinfunction "NC_6") (pintype "input+no_connect"))
    )
    (net (code "49") (name "unconnected-(U5-Pad3)") (class "Default")
      (node (ref "U5") (pin "3") (pinfunction "3_3") (pintype "input+no_connect"))
    )
  )
)
